# BackupPower.net
KiCad netlist of a schematic drawn in Altium Designer
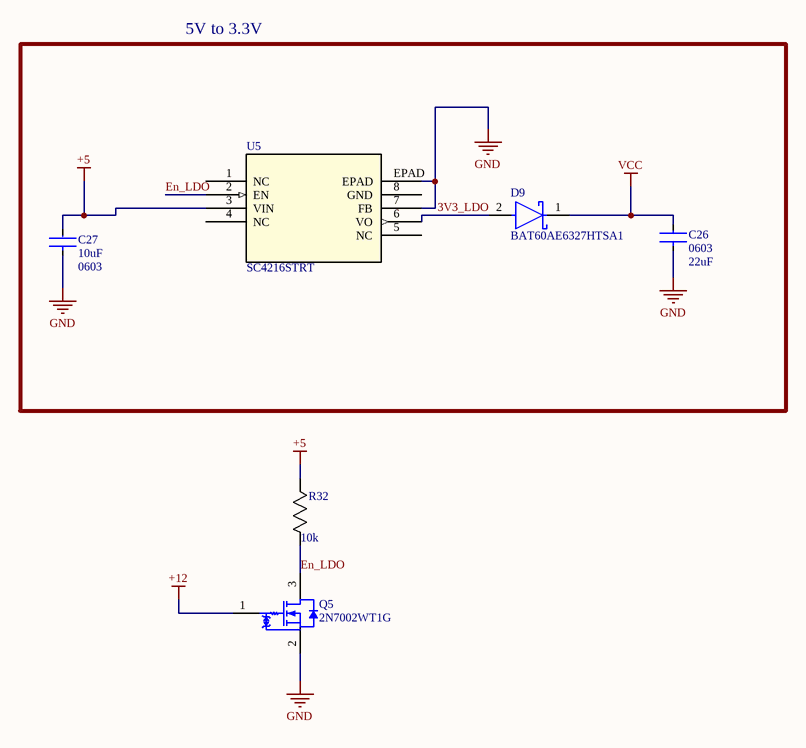
[diagram p0: BackupPower.SchDoc]

(export (version "E")
  (design (tool "Eeschema 10.0.6"))
  (components
    (comp (ref "C26")
      (value "GRM188R60G226MEA0D")
      (footprint "FP-GRM188-0_2-MFG")
      (description "Chip Multilayer Ceramic Capacitors for General Purpose, 0603, 22uF, X5R, 15%, 20%, 4V")
      (fields
        (field (name "CASE/PACKAGE") "0603")
        (field (name "VOLTAGE") "4V")
        (field (name "TOLERANCE") "20%")
        (field (name "CAPACITANCE") "22uF")
      )
      (libsource (lib "Altium Content Vault") (part "11868f565c42a9108669ba33697ecf6"))
    )
    (comp (ref "C27")
      (value "CL10A106MQ8NNNC")
      (footprint "FP-CL10-IPC_C")
      (description "Cap Ceramic 10uF 6.3V X5R ±20% Pad SMD 0603 +85°C T/R")
      (fields
        (field (name "CAPACITANCE") "10uF")
        (field (name "CASE/PACKAGE") "0603")
        (field (name "VOLTAGE") "6.3V")
        (field (name "TOLERANCE") "20%")
      )
      (libsource (lib "Altium Content Vault") (part "b4654b650e69147ec39a6b967a45e02"))
    )
    (comp (ref "D9")
      (value "BAT60AE6327HTSA1")
      (footprint "FP-PG-SOD323-2-IPC_C")
      (description "DIODE SCHOTTKY 10V 3A SOD323-2")
      (libsource (lib "Altium Content Vault") (part "1d6ec82d83fb6aee721767c19dac4b9"))
    )
    (comp (ref "Q5")
      (value "2N7002WT1G")
      (footprint "ONSC-SC-70-3-419-04_V")
      (description "Small Signal MOSFET, 60 V, 340 mA, Single, N-Channel, 3-Pin SC70, Pb-Free, Tape and Reel")
      (fields (field (name "MANUFACTURER") "On Semiconductor"))
      (libsource (lib "Altium Content Vault") (part "ONSC-NMOS-G1S2D3-3_C"))
    )
    (comp (ref "R32")
      (value "RC0603FR-0710KL")
      (footprint "RC0603N_YAG")
      (description "RES SMD 10kO 1% 1/10W 0603")
      (fields
        (field (name "R") "10k")
        (field (name "COPYRIGHT") "Copyright (C) 2025 Ultra Librarian. All rights reserved.")
      )
      (libsource (lib "WiCAN_lib") (part "RC0603FR-0710KL"))
    )
    (comp (ref "U5")
      (value "SC4216STRT")
      (footprint "SOIC-8-EDP_SEM")
      (description "Linear Voltage Regulator IC Positive Adjustable (Fixed) 1 Output 3A 8-SOIC, EDP")
      (fields (field (name "COPYRIGHT") "Copyright (C) 2026 Ultra Librarian. All rights reserved."))
      (libsource (lib "WiCAN_lib") (part "SC4216STRT"))
    )
  )
  (nets
    (net (code "1") (name "+5") (class "Default")
      (node (ref "C27") (pin "2") (pinfunction "2_2") (pintype "passive"))
      (node (ref "R32") (pin "2") (pinfunction "2_2") (pintype "passive"))
      (node (ref "U5") (pin "3") (pinfunction "VIN_3") (pintype "power_in"))
    )
    (net (code "2") (name "+12") (class "Default")
      (node (ref "Q5") (pin "1") (pinfunction "G_1") (pintype "passive"))
    )
    (net (code "3") (name "/3V3_LDO") (class "Default")
      (node (ref "D9") (pin "2") (pinfunction "A_2") (pintype "passive"))
      (node (ref "U5") (pin "6") (pinfunction "VO_6") (pintype "output"))
    )
    (net (code "4") (name "/En_LDO") (class "Default")
      (node (ref "Q5") (pin "3") (pinfunction "D_3") (pintype "passive"))
      (node (ref "R32") (pin "1") (pinfunction "1_1") (pintype "passive"))
      (node (ref "U5") (pin "2") (pinfunction "EN_2") (pintype "input"))
    )
    (net (code "5") (name "GND") (class "Default")
      (node (ref "C26") (pin "1") (pinfunction "1_1") (pintype "passive"))
      (node (ref "C27") (pin "1") (pinfunction "1_1") (pintype "passive"))
      (node (ref "Q5") (pin "2") (pinfunction "S_2") (pintype "passive"))
      (node (ref "U5") (pin "7") (pinfunction "FB_7") (pintype "passive"))
      (node (ref "U5") (pin "EPAD") (pinfunction "EPAD_EPAD") (pintype "power_in"))
    )
    (net (code "6") (name "VCC") (class "Default")
      (node (ref "C26") (pin "2") (pinfunction "2_2") (pintype "passive"))
      (node (ref "D9") (pin "1") (pinfunction "C_1") (pintype "passive"))
    )
    (net (code "7") (name "unconnected-(U5-GND-Pad8)") (class "Default")
      (node (ref "U5") (pin "8") (pinfunction "GND_8") (pintype "power_in"))
    )
    (net (code "8") (name "unconnected-(U5-NC-Pad1)") (class "Default")
      (node (ref "U5") (pin "1") (pinfunction "NC_1") (pintype "passive"))
    )
    (net (code "9") (name "unconnected-(U5-NC-Pad4)") (class "Default")
      (node (ref "U5") (pin "4") (pinfunction "NC_4") (pintype "passive"))
    )
    (net (code "10") (name "unconnected-(U5-NC-Pad5)") (class "Default")
      (node (ref "U5") (pin "5") (pinfunction "NC_5") (pintype "passive"))
    )
  )
)
